# BH1730FVC_top.net
KiCad netlist of a schematic drawn in Altium Designer
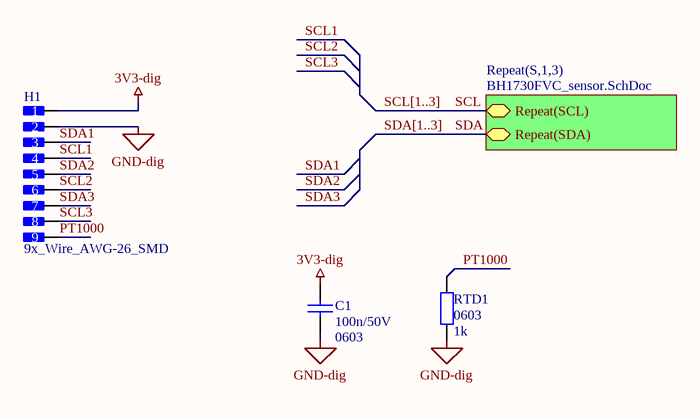
[diagram p0: BH1730FVC_top.SchDoc]

(export (version "E")
  (design (tool "Eeschema 10.0.6"))
  (components
    (comp (ref "C1")
      (value "100n/50V")
      (footprint "SMD_Capacitor_0603")
      (description "Ceramic Cap Kemet COTS 100n/50V X7R 0603")
      (fields
        (field (name "MANUFACTURER") "Kemet")
        (field (name "MANUFACTURERPARTNUMBER") "C0603T104K5RALTU")
        (field (name "PACKAGE") "0603")
      )
      (libsource (lib "capacitors") (part "Cer_C0603T104K5RALTU"))
    )
    (comp (ref "H1")
      (value "9x_Wire_AWG-26_SMD")
      (footprint "Wire_AWG-26_x9_SMD")
      (description "9 x SMD pads for an AWG-26 wire with stress relief, pitch 1.27mm.")
      (libsource (lib "connectors_printed-circuit-board") (part "Wire_AWG-26_x9_SMD_1"))
    )
    (comp (ref "RTD1")
      (value "1k")
      (footprint "SMD_Resistor_0603")
      (description "PT1000 Vishay PTS060301B100RP100")
      (fields
        (field (name "MANUFACTURER") "Vishay")
        (field (name "MANUFACTURERPARTNUMBER") "PTS060301B100RP100")
        (field (name "PACKAGE") "0603")
      )
      (libsource (lib "resistors") (part "PTS060301B100RP100"))
    )
  )
  (nets
    (net (code "1") (name "/PT1000") (class "Default")
      (node (ref "H1") (pin "9") (pinfunction "9_9") (pintype "passive"))
      (node (ref "RTD1") (pin "1") (pinfunction "1_1") (pintype "passive"))
    )
    (net (code "3") (name "/SCL1") (class "Default")
      (node (ref "H1") (pin "4") (pinfunction "4_4") (pintype "passive"))
    )
    (net (code "4") (name "/SCL2") (class "Default")
      (node (ref "H1") (pin "6") (pinfunction "6_6") (pintype "passive"))
    )
    (net (code "5") (name "/SCL3") (class "Default")
      (node (ref "H1") (pin "8") (pinfunction "8_8") (pintype "passive"))
    )
    (net (code "8") (name "/SDA1") (class "Default")
      (node (ref "H1") (pin "3") (pinfunction "3_3") (pintype "passive"))
    )
    (net (code "9") (name "/SDA2") (class "Default")
      (node (ref "H1") (pin "5") (pinfunction "5_5") (pintype "passive"))
    )
    (net (code "10") (name "/SDA3") (class "Default")
      (node (ref "H1") (pin "7") (pinfunction "7_7") (pintype "passive"))
    )
    (net (code "12") (name "3V3-dig") (class "Default")
      (node (ref "C1") (pin "1") (pinfunction "1_1") (pintype "passive"))
      (node (ref "H1") (pin "1") (pinfunction "1_1") (pintype "passive"))
    )
    (net (code "13") (name "GND-dig") (class "Default")
      (node (ref "C1") (pin "2") (pinfunction "2_2") (pintype "passive"))
      (node (ref "H1") (pin "2") (pinfunction "2_2") (pintype "passive"))
      (node (ref "RTD1") (pin "2") (pinfunction "2_2") (pintype "passive"))
    )
  )
)
